# ClockDriver.net
KiCad netlist of a schematic drawn in Altium Designer
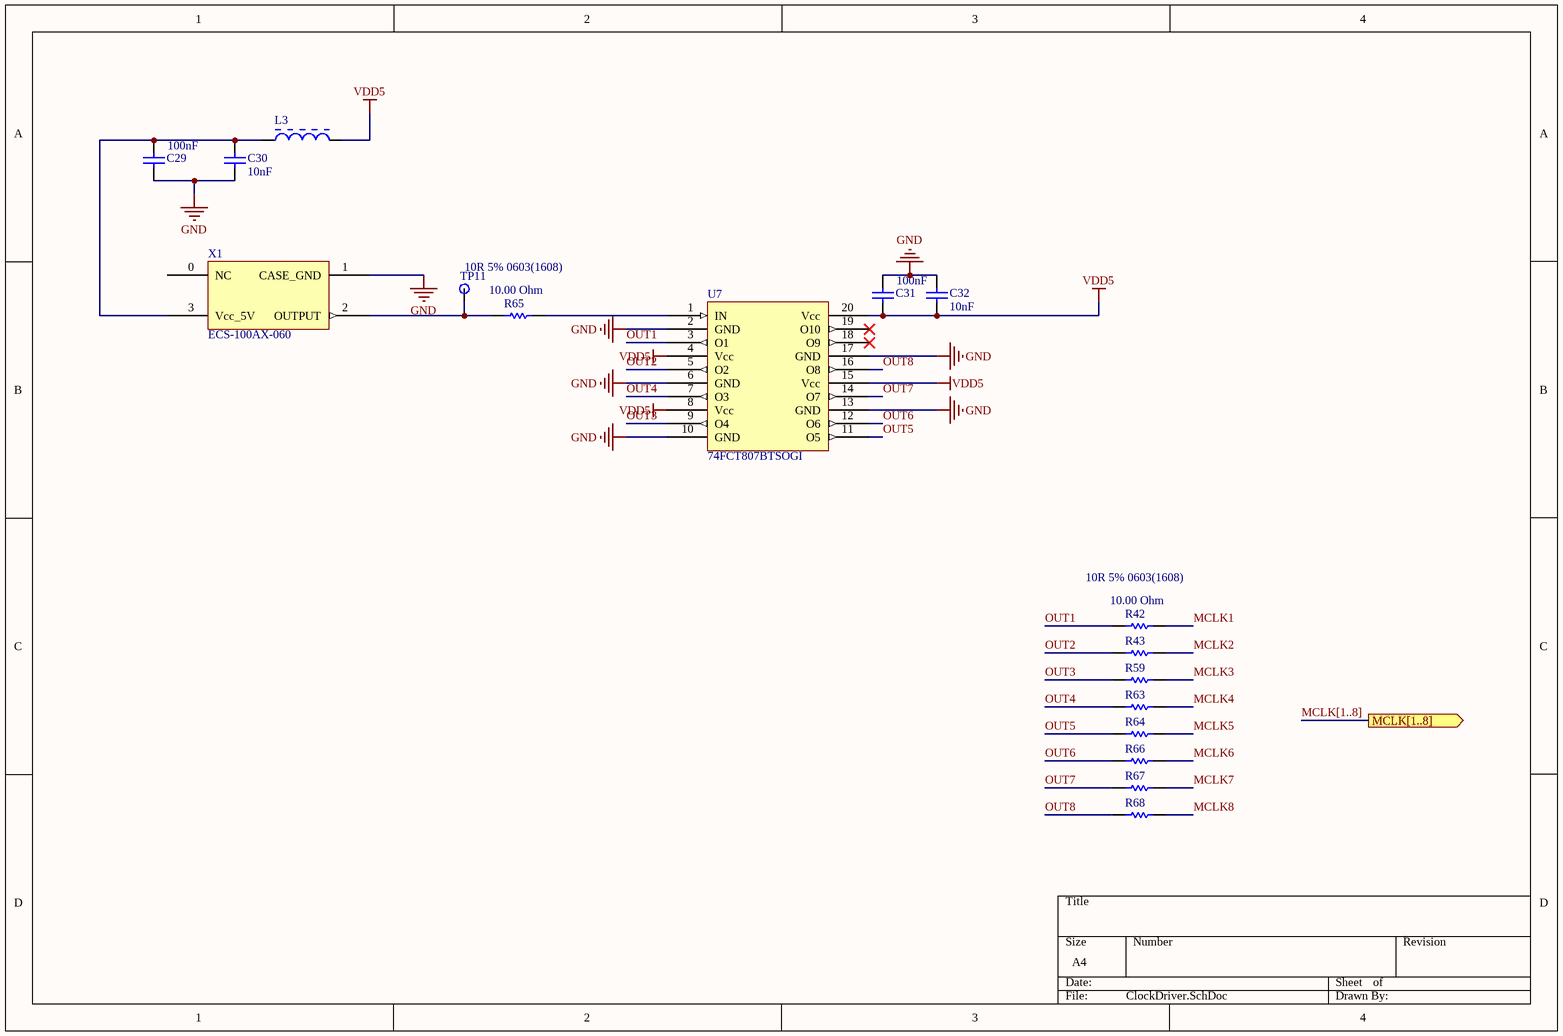
[diagram p0: ClockDriver.SchDoc]

(export (version "E")
  (design (tool "Eeschema 10.0.6"))
  (components
    (comp (ref "C29")
      (value "100nF")
      (footprint "CAPC0603(1608)100_M")
      (description "CAP 100nF 25V ±10% 0603 (1608 Metric) Thickness 1mm SMD")
      (fields (field (name "TOLERANCE") "Â±10%") (field (name "Comment") "CAP 100nF 25V 0603(1608)"))
      (libsource (lib "Altium Content Vault") (part "CMP-1035-02588-1"))
    )
    (comp (ref "C30")
      (value "10nF")
      (footprint "CAPC0603(1608)100_N")
      (description "CAP 10nF 25V ±10% 0603 (1608 Metric) Thickness 1mm SMD")
      (fields (field (name "TOLERANCE") "Â±10%") (field (name "Comment") "CAP 10nF 25V 0603(1608)"))
      (libsource (lib "Altium Content Vault") (part "CMP-1035-02317-1"))
    )
    (comp (ref "C31")
      (value "100nF")
      (footprint "CAPC0603(1608)100_M")
      (description "CAP 100nF 25V ±10% 0603 (1608 Metric) Thickness 1mm SMD")
      (fields (field (name "TOLERANCE") "Â±10%") (field (name "Comment") "CAP 100nF 25V 0603(1608)"))
      (libsource (lib "Altium Content Vault") (part "CMP-1035-02588-1"))
    )
    (comp (ref "C32")
      (value "10nF")
      (footprint "CAPC0603(1608)100_N")
      (description "CAP 10nF 25V ±10% 0603 (1608 Metric) Thickness 1mm SMD")
      (fields (field (name "TOLERANCE") "Â±10%") (field (name "Comment") "CAP 10nF 25V 0603(1608)"))
      (libsource (lib "Altium Content Vault") (part "CMP-1035-02317-1"))
    )
    (comp (ref "L3")
      (value "~")
      (footprint "BOUR-MH1608_V")
      (description "Chip Bead, 600 Ohm, 1 A, -55 to 125 degC, 2-Pin SMD (0603), RoHS, Tape and Reel")
      (fields (field (name "MANUFACTURER") "Bourns") (field (name "MANUFACTURER PART NUMBER") "742792651"))
      (libsource (lib "Altium Content Vault") (part "CMP-2000-06698-1"))
    )
    (comp (ref "R42")
      (value "10R 5% 0603(1608)")
      (footprint "RESC0603(1608)_M")
      (description "10R 0.1W 5% 0603 (1608 Metric)  SMD")
      (fields
        (field (name "TOLERANCE") "5 %")
        (field (name "POWER") "0.1 W")
        (field (name "ALTIUM_VALUE") "10.00 Ohm")
      )
      (libsource (lib "Altium Content Vault") (part "CMP-1012-00026-1"))
    )
    (comp (ref "R43")
      (value "10R 5% 0603(1608)")
      (footprint "RESC0603(1608)_M")
      (description "10R 0.1W 5% 0603 (1608 Metric)  SMD")
      (fields (field (name "TOLERANCE") "5 %") (field (name "POWER") "0.1 W"))
      (libsource (lib "Altium Content Vault") (part "CMP-1012-00026-1"))
    )
    (comp (ref "R59")
      (value "10R 5% 0603(1608)")
      (footprint "RESC0603(1608)_M")
      (description "10R 0.1W 5% 0603 (1608 Metric)  SMD")
      (fields (field (name "TOLERANCE") "5 %") (field (name "POWER") "0.1 W"))
      (libsource (lib "Altium Content Vault") (part "CMP-1012-00026-1"))
    )
    (comp (ref "R63")
      (value "10R 5% 0603(1608)")
      (footprint "RESC0603(1608)_M")
      (description "10R 0.1W 5% 0603 (1608 Metric)  SMD")
      (fields (field (name "TOLERANCE") "5 %") (field (name "POWER") "0.1 W"))
      (libsource (lib "Altium Content Vault") (part "CMP-1012-00026-1"))
    )
    (comp (ref "R64")
      (value "10R 5% 0603(1608)")
      (footprint "RESC0603(1608)_M")
      (description "10R 0.1W 5% 0603 (1608 Metric)  SMD")
      (fields (field (name "TOLERANCE") "5 %") (field (name "POWER") "0.1 W"))
      (libsource (lib "Altium Content Vault") (part "CMP-1012-00026-1"))
    )
    (comp (ref "R65")
      (value "10R 5% 0603(1608)")
      (footprint "RESC0603(1608)_M")
      (description "10R 0.1W 5% 0603 (1608 Metric)  SMD")
      (fields
        (field (name "TOLERANCE") "5 %")
        (field (name "POWER") "0.1 W")
        (field (name "ALTIUM_VALUE") "10.00 Ohm")
      )
      (libsource (lib "Altium Content Vault") (part "CMP-1012-00026-1"))
    )
    (comp (ref "R66")
      (value "10R 5% 0603(1608)")
      (footprint "RESC0603(1608)_M")
      (description "10R 0.1W 5% 0603 (1608 Metric)  SMD")
      (fields (field (name "TOLERANCE") "5 %") (field (name "POWER") "0.1 W"))
      (libsource (lib "Altium Content Vault") (part "CMP-1012-00026-1"))
    )
    (comp (ref "R67")
      (value "10R 5% 0603(1608)")
      (footprint "RESC0603(1608)_M")
      (description "10R 0.1W 5% 0603 (1608 Metric)  SMD")
      (fields (field (name "TOLERANCE") "5 %") (field (name "POWER") "0.1 W"))
      (libsource (lib "Altium Content Vault") (part "CMP-1012-00026-1"))
    )
    (comp (ref "R68")
      (value "10R 5% 0603(1608)")
      (footprint "RESC0603(1608)_M")
      (description "10R 0.1W 5% 0603 (1608 Metric)  SMD")
      (fields (field (name "TOLERANCE") "5 %") (field (name "POWER") "0.1 W"))
      (libsource (lib "Altium Content Vault") (part "CMP-1012-00026-1"))
    )
    (comp (ref "TP11")
      (value "Testpoint")
      (footprint "0603 PROBE PAD")
      (description "0.063\" x 0.031\" x 0.045\" (1.60mm x 0.80mm x 1.15mm)")
      (libsource (lib "testpoint") (part "Testpoint"))
    )
    (comp (ref "U7")
      (value "74FCT807BTSOGI")
      (footprint "CLOCK DRIVER 10:1")
      (description "IC CLK BUFFER 1:10 100MHZ 20SOIC")
      (fields
        (field (name "MANUFACTURER") "IDT, Integrated Device Technology Inc")
        (field (name "PUBLISHER") "Altium Limited")
      )
      (libsource (lib "AnserEMT") (part "74FCT807BTSOGI"))
    )
    (comp (ref "X1")
      (value "ECS-100AX-060")
      (footprint "ECS-100AX-060")
      (description "OSC XO 6.000MHZ TTL PC PIN")
      (fields (field (name "MANUFACTURER") "ECS Inc.") (field (name "PUBLISHER") "Altium Limited"))
      (libsource (lib "AnserEMT") (part "ECS-100AX-060"))
    )
  )
  (nets
    (net (code "1") (name "/MCLK1") (class "Default")
      (node (ref "R42") (pin "2") (pinfunction "2_2") (pintype "passive"))
    )
    (net (code "2") (name "/MCLK2") (class "Default")
      (node (ref "R43") (pin "2") (pinfunction "2_2") (pintype "passive"))
    )
    (net (code "3") (name "/MCLK3") (class "Default")
      (node (ref "R59") (pin "2") (pinfunction "2_2") (pintype "passive"))
    )
    (net (code "4") (name "/MCLK4") (class "Default")
      (node (ref "R63") (pin "2") (pinfunction "2_2") (pintype "passive"))
    )
    (net (code "5") (name "/MCLK5") (class "Default")
      (node (ref "R64") (pin "2") (pinfunction "2_2") (pintype "passive"))
    )
    (net (code "6") (name "/MCLK6") (class "Default")
      (node (ref "R66") (pin "2") (pinfunction "2_2") (pintype "passive"))
    )
    (net (code "7") (name "/MCLK7") (class "Default")
      (node (ref "R67") (pin "2") (pinfunction "2_2") (pintype "passive"))
    )
    (net (code "8") (name "/MCLK8") (class "Default")
      (node (ref "R68") (pin "2") (pinfunction "2_2") (pintype "passive"))
    )
    (net (code "10") (name "/OUT1") (class "Default")
      (node (ref "R42") (pin "1") (pinfunction "1_1") (pintype "passive"))
      (node (ref "U7") (pin "3") (pinfunction "O1_3") (pintype "output"))
    )
    (net (code "11") (name "/OUT2") (class "Default")
      (node (ref "R43") (pin "1") (pinfunction "1_1") (pintype "passive"))
      (node (ref "U7") (pin "5") (pinfunction "O2_5") (pintype "output"))
    )
    (net (code "12") (name "/OUT3") (class "Default")
      (node (ref "R59") (pin "1") (pinfunction "1_1") (pintype "passive"))
      (node (ref "U7") (pin "9") (pinfunction "O4_9") (pintype "output"))
    )
    (net (code "13") (name "/OUT4") (class "Default")
      (node (ref "R63") (pin "1") (pinfunction "1_1") (pintype "passive"))
      (node (ref "U7") (pin "7") (pinfunction "O3_7") (pintype "output"))
    )
    (net (code "14") (name "/OUT5") (class "Default")
      (node (ref "R64") (pin "1") (pinfunction "1_1") (pintype "passive"))
      (node (ref "U7") (pin "11") (pinfunction "O5_11") (pintype "output"))
    )
    (net (code "15") (name "/OUT6") (class "Default")
      (node (ref "R66") (pin "1") (pinfunction "1_1") (pintype "passive"))
      (node (ref "U7") (pin "12") (pinfunction "O6_12") (pintype "output"))
    )
    (net (code "16") (name "/OUT7") (class "Default")
      (node (ref "R67") (pin "1") (pinfunction "1_1") (pintype "passive"))
      (node (ref "U7") (pin "14") (pinfunction "O7_14") (pintype "output"))
    )
    (net (code "17") (name "/OUT8") (class "Default")
      (node (ref "R68") (pin "1") (pinfunction "1_1") (pintype "passive"))
      (node (ref "U7") (pin "16") (pinfunction "O8_16") (pintype "output"))
    )
    (net (code "18") (name "GND") (class "Default")
      (node (ref "C29") (pin "2") (pinfunction "2_2") (pintype "passive"))
      (node (ref "C30") (pin "1") (pinfunction "1_1") (pintype "passive"))
      (node (ref "C31") (pin "1") (pinfunction "1_1") (pintype "passive"))
      (node (ref "C32") (pin "2") (pinfunction "2_2") (pintype "passive"))
      (node (ref "U7") (pin "10") (pinfunction "GND_10") (pintype "power_in"))
      (node (ref "U7") (pin "13") (pinfunction "GND_13") (pintype "power_in"))
      (node (ref "U7") (pin "17") (pinfunction "GND_17") (pintype "power_in"))
      (node (ref "U7") (pin "2") (pinfunction "GND_2") (pintype "power_in"))
      (node (ref "U7") (pin "6") (pinfunction "GND_6") (pintype "power_in"))
      (node (ref "X1") (pin "1") (pinfunction "CASE_GND_1") (pintype "power_in"))
    )
    (net (code "19") (name "Net-(U7-IN)") (class "Default")
      (node (ref "R65") (pin "2") (pinfunction "2_2") (pintype "passive"))
      (node (ref "U7") (pin "1") (pinfunction "IN_1") (pintype "input"))
    )
    (net (code "20") (name "Net-(X1-OUTPUT)") (class "Default")
      (node (ref "R65") (pin "1") (pinfunction "1_1") (pintype "passive"))
      (node (ref "TP11") (pin "0") (pintype "passive"))
      (node (ref "X1") (pin "2") (pinfunction "OUTPUT_2") (pintype "output"))
    )
    (net (code "21") (name "Net-(X1-Vcc_5V)") (class "Default")
      (node (ref "C29") (pin "1") (pinfunction "1_1") (pintype "passive"))
      (node (ref "C30") (pin "2") (pinfunction "2_2") (pintype "passive"))
      (node (ref "L3") (pin "1") (pinfunction "1_1") (pintype "passive"))
      (node (ref "X1") (pin "3") (pinfunction "Vcc_5V_3") (pintype "power_in"))
    )
    (net (code "22") (name "VDD5") (class "Default")
      (node (ref "C31") (pin "2") (pinfunction "2_2") (pintype "passive"))
      (node (ref "C32") (pin "1") (pinfunction "1_1") (pintype "passive"))
      (node (ref "L3") (pin "2") (pinfunction "2_2") (pintype "passive"))
      (node (ref "U7") (pin "15") (pinfunction "Vcc_15") (pintype "power_in"))
      (node (ref "U7") (pin "20") (pinfunction "Vcc_20") (pintype "power_in"))
      (node (ref "U7") (pin "4") (pinfunction "Vcc_4") (pintype "power_in"))
      (node (ref "U7") (pin "8") (pinfunction "Vcc_8") (pintype "power_in"))
    )
    (net (code "23") (name "unconnected-(U7-O9-Pad18)") (class "Default")
      (node (ref "U7") (pin "18") (pinfunction "O9_18") (pintype "output+no_connect"))
    )
    (net (code "24") (name "unconnected-(U7-O10-Pad19)") (class "Default")
      (node (ref "U7") (pin "19") (pinfunction "O10_19") (pintype "output+no_connect"))
    )
    (net (code "25") (name "unconnected-(X1-NC-Pad0)") (class "Default")
      (node (ref "X1") (pin "0") (pinfunction "NC_0") (pintype "passive"))
    )
  )
)
